# switches.net
KiCad netlist of a schematic drawn in Altium Designer
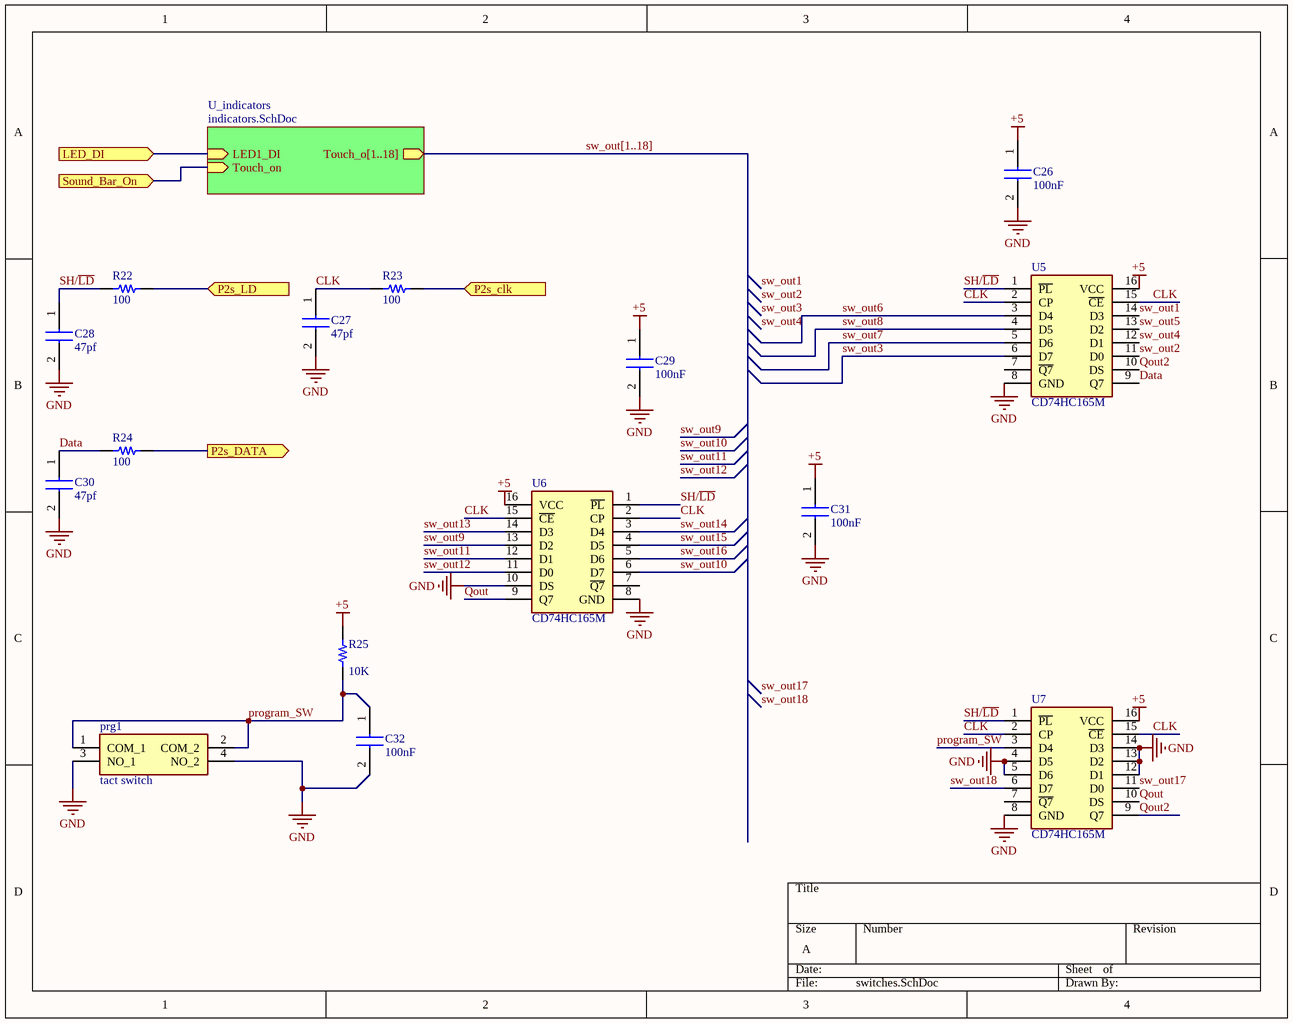
[diagram p0: switches.SchDoc]

(export (version "E")
  (design (tool "Eeschema 10.0.6"))
  (components
    (comp (ref "C26")
      (value "100nF")
      (footprint "0603C")
      (description "100 nF Ceramic capacitor")
      (fields
        (field (name "MANUFACTURER_PART_NUMBER") "C1206C104Z5UACTU")
        (field (name "MOUSER PART NUMBER") "80-C1206C104Z5U")
      )
      (libsource (lib "*") (part "C1206C104Z5UACTU"))
    )
    (comp (ref "C27")
      (value "47pf")
      (footprint "0603C")
      (description "100 nF Ceramic capacitor")
      (fields
        (field (name "MANUFACTURER_PART_NUMBER") "C1206C104Z5UACTU")
        (field (name "MOUSER PART NUMBER") "80-C1206C104Z5U")
      )
      (libsource (lib "*") (part "C1206C104Z5UACTU"))
    )
    (comp (ref "C28")
      (value "47pf")
      (footprint "0603C")
      (description "100 nF Ceramic capacitor")
      (fields
        (field (name "MANUFACTURER_PART_NUMBER") "C1206C104Z5UACTU")
        (field (name "MOUSER PART NUMBER") "80-C1206C104Z5U")
      )
      (libsource (lib "*") (part "C1206C104Z5UACTU"))
    )
    (comp (ref "C29")
      (value "100nF")
      (footprint "0603C")
      (description "100 nF Ceramic capacitor")
      (fields
        (field (name "MANUFACTURER_PART_NUMBER") "C1206C104Z5UACTU")
        (field (name "MOUSER PART NUMBER") "80-C1206C104Z5U")
      )
      (libsource (lib "*") (part "C1206C104Z5UACTU"))
    )
    (comp (ref "C30")
      (value "47pf")
      (footprint "0603C")
      (description "100 nF Ceramic capacitor")
      (fields
        (field (name "MANUFACTURER_PART_NUMBER") "C1206C104Z5UACTU")
        (field (name "MOUSER PART NUMBER") "80-C1206C104Z5U")
      )
      (libsource (lib "*") (part "C1206C104Z5UACTU"))
    )
    (comp (ref "C31")
      (value "100nF")
      (footprint "0603C")
      (description "100 nF Ceramic capacitor")
      (fields
        (field (name "MANUFACTURER_PART_NUMBER") "C1206C104Z5UACTU")
        (field (name "MOUSER PART NUMBER") "80-C1206C104Z5U")
      )
      (libsource (lib "*") (part "C1206C104Z5UACTU"))
    )
    (comp (ref "C32")
      (value "100nF")
      (footprint "0603C")
      (description "100 nF Ceramic capacitor")
      (fields
        (field (name "MANUFACTURER_PART_NUMBER") "C1206C104Z5UACTU")
        (field (name "MOUSER PART NUMBER") "80-C1206C104Z5U")
      )
      (libsource (lib "*") (part "C1206C104Z5UACTU"))
    )
    (comp (ref "prg1")
      (value "tact switch")
      (footprint "DTSM63NVB")
      (description "Push Button SMD - 4PIN")
      (fields
        (field (name "MANUFACTURER_PART_NUMBER") "DTSM-66R-V-T/R")
        (field (name "MOUSER PART NUMBER") "113-DTSM66RVTR")
      )
      (libsource (lib "*") (part "DTSM-66R-V-T_R"))
    )
    (comp (ref "R22")
      (value "100")
      (footprint "0603R")
      (description "RES SMD 10K OHM 5% 1/8W 0805")
      (fields (field (name "PART NUMBER") "CRCW080510K0JNEAIF") (field (name "MANUFACTURER") "Vishay Dale"))
      (libsource (lib "Celestial Altium Library - altium_library") (part "Resistor"))
    )
    (comp (ref "R23")
      (value "100")
      (footprint "0603R")
      (description "RES SMD 10K OHM 5% 1/8W 0805")
      (fields (field (name "PART NUMBER") "CRCW080510K0JNEAIF") (field (name "MANUFACTURER") "Vishay Dale"))
      (libsource (lib "Celestial Altium Library - altium_library") (part "Resistor"))
    )
    (comp (ref "R24")
      (value "100")
      (footprint "RES1206 _(3216X08L)")
      (description "RES SMD 10K OHM 5% 1/8W 0805")
      (fields (field (name "PART NUMBER") "CRCW080510K0JNEAIF") (field (name "MANUFACTURER") "Vishay Dale"))
      (libsource (lib "Celestial Altium Library - altium_library") (part "Resistor"))
    )
    (comp (ref "R25")
      (value "10K")
      (footprint "0603R")
      (description "RES SMD 0603")
      (fields (field (name "PART NUMBER") "RCS0805100KFKEA"))
      (libsource (lib "lamp control-ver2") (part "Resistor"))
    )
    (comp (ref "U5")
      (value "CD74HC165M")
      (footprint "SOIC127P600X175-16N")
      (description "Integrated Circuit")
      (fields (field (name "MOUSER PART NUMBER") "595-CD74HC165M"))
      (libsource (lib "SamacSys") (part "CD74HC165M"))
    )
    (comp (ref "U6")
      (value "CD74HC165M")
      (footprint "SOIC127P600X175-16N")
      (description "Integrated Circuit")
      (fields (field (name "MOUSER PART NUMBER") "595-CD74HC165M"))
      (libsource (lib "") (part "CD74HC165M_1"))
    )
    (comp (ref "U7")
      (value "CD74HC165M")
      (footprint "SOIC127P600X175-16N")
      (description "Integrated Circuit")
      (fields (field (name "MOUSER PART NUMBER") "595-CD74HC165M"))
      (libsource (lib "SamacSys") (part "CD74HC165M"))
    )
  )
  (nets
    (net (code "1") (name "+5") (class "Default")
      (node (ref "C26") (pin "1") (pinfunction "1_1") (pintype "passive"))
      (node (ref "C29") (pin "1") (pinfunction "1_1") (pintype "passive"))
      (node (ref "C31") (pin "1") (pinfunction "1_1") (pintype "passive"))
      (node (ref "R25") (pin "2") (pinfunction "2_2") (pintype "passive"))
      (node (ref "U5") (pin "16") (pinfunction "VCC_16") (pintype "passive"))
      (node (ref "U6") (pin "16") (pinfunction "VCC_16") (pintype "passive"))
      (node (ref "U7") (pin "16") (pinfunction "VCC_16") (pintype "passive"))
    )
    (net (code "2") (name "/CLK") (class "Default")
      (node (ref "C27") (pin "1") (pinfunction "1_1") (pintype "passive"))
      (node (ref "R23") (pin "2") (pinfunction "2_2") (pintype "passive"))
      (node (ref "U5") (pin "15") (pinfunction "~{CE}_15") (pintype "passive"))
      (node (ref "U5") (pin "2") (pinfunction "CP_2") (pintype "passive"))
      (node (ref "U6") (pin "15") (pinfunction "~{CE}_15") (pintype "passive"))
      (node (ref "U6") (pin "2") (pinfunction "CP_2") (pintype "passive"))
      (node (ref "U7") (pin "15") (pinfunction "~{CE}_15") (pintype "passive"))
      (node (ref "U7") (pin "2") (pinfunction "CP_2") (pintype "passive"))
    )
    (net (code "3") (name "/Data") (class "Default")
      (node (ref "C30") (pin "1") (pinfunction "1_1") (pintype "passive"))
      (node (ref "R24") (pin "2") (pinfunction "2_2") (pintype "passive"))
      (node (ref "U5") (pin "9") (pinfunction "Q7_9") (pintype "passive"))
    )
    (net (code "5") (name "/P2s_DATA") (class "Default")
      (node (ref "R24") (pin "1") (pinfunction "1_1") (pintype "passive"))
    )
    (net (code "6") (name "/P2s_LD") (class "Default")
      (node (ref "R22") (pin "1") (pinfunction "1_1") (pintype "passive"))
    )
    (net (code "7") (name "/P2s_clk") (class "Default")
      (node (ref "R23") (pin "1") (pinfunction "1_1") (pintype "passive"))
    )
    (net (code "8") (name "/Qout") (class "Default")
      (node (ref "U6") (pin "9") (pinfunction "Q7_9") (pintype "passive"))
      (node (ref "U7") (pin "10") (pinfunction "DS_10") (pintype "passive"))
    )
    (net (code "9") (name "/Qout2") (class "Default")
      (node (ref "U5") (pin "10") (pinfunction "DS_10") (pintype "passive"))
      (node (ref "U7") (pin "9") (pinfunction "Q7_9") (pintype "passive"))
    )
    (net (code "10") (name "/SH{slash}~{LD}") (class "Default")
      (node (ref "C28") (pin "1") (pinfunction "1_1") (pintype "passive"))
      (node (ref "R22") (pin "2") (pinfunction "2_2") (pintype "passive"))
      (node (ref "U5") (pin "1") (pinfunction "~{PL}_1") (pintype "passive"))
      (node (ref "U6") (pin "1") (pinfunction "~{PL}_1") (pintype "passive"))
      (node (ref "U7") (pin "1") (pinfunction "~{PL}_1") (pintype "passive"))
    )
    (net (code "12") (name "/program_SW") (class "Default")
      (node (ref "C32") (pin "1") (pinfunction "1_1") (pintype "passive"))
      (node (ref "R25") (pin "1") (pinfunction "1_1") (pintype "passive"))
      (node (ref "U7") (pin "3") (pinfunction "D4_3") (pintype "passive"))
      (node (ref "prg1") (pin "1") (pinfunction "COM_1_1") (pintype "passive"))
      (node (ref "prg1") (pin "2") (pinfunction "COM_2_2") (pintype "passive"))
    )
    (net (code "13") (name "/sw_out1") (class "Default")
      (node (ref "U5") (pin "14") (pinfunction "D3_14") (pintype "passive"))
    )
    (net (code "14") (name "/sw_out2") (class "Default")
      (node (ref "U5") (pin "11") (pinfunction "D0_11") (pintype "passive"))
    )
    (net (code "15") (name "/sw_out3") (class "Default")
      (node (ref "U5") (pin "6") (pinfunction "D7_6") (pintype "passive"))
    )
    (net (code "16") (name "/sw_out4") (class "Default")
      (node (ref "U5") (pin "12") (pinfunction "D1_12") (pintype "passive"))
    )
    (net (code "17") (name "/sw_out5") (class "Default")
      (node (ref "U5") (pin "13") (pinfunction "D2_13") (pintype "passive"))
    )
    (net (code "18") (name "/sw_out6") (class "Default")
      (node (ref "U5") (pin "3") (pinfunction "D4_3") (pintype "passive"))
    )
    (net (code "19") (name "/sw_out7") (class "Default")
      (node (ref "U5") (pin "5") (pinfunction "D6_5") (pintype "passive"))
    )
    (net (code "20") (name "/sw_out8") (class "Default")
      (node (ref "U5") (pin "4") (pinfunction "D5_4") (pintype "passive"))
    )
    (net (code "21") (name "/sw_out9") (class "Default")
      (node (ref "U6") (pin "13") (pinfunction "D2_13") (pintype "passive"))
    )
    (net (code "22") (name "/sw_out10") (class "Default")
      (node (ref "U6") (pin "6") (pinfunction "D7_6") (pintype "passive"))
    )
    (net (code "23") (name "/sw_out11") (class "Default")
      (node (ref "U6") (pin "12") (pinfunction "D1_12") (pintype "passive"))
    )
    (net (code "24") (name "/sw_out12") (class "Default")
      (node (ref "U6") (pin "11") (pinfunction "D0_11") (pintype "passive"))
    )
    (net (code "25") (name "/sw_out13") (class "Default")
      (node (ref "U6") (pin "14") (pinfunction "D3_14") (pintype "passive"))
    )
    (net (code "26") (name "/sw_out14") (class "Default")
      (node (ref "U6") (pin "3") (pinfunction "D4_3") (pintype "passive"))
    )
    (net (code "27") (name "/sw_out15") (class "Default")
      (node (ref "U6") (pin "4") (pinfunction "D5_4") (pintype "passive"))
    )
    (net (code "28") (name "/sw_out16") (class "Default")
      (node (ref "U6") (pin "5") (pinfunction "D6_5") (pintype "passive"))
    )
    (net (code "29") (name "/sw_out17") (class "Default")
      (node (ref "U7") (pin "11") (pinfunction "D0_11") (pintype "passive"))
    )
    (net (code "30") (name "/sw_out18") (class "Default")
      (node (ref "U7") (pin "6") (pinfunction "D7_6") (pintype "passive"))
    )
    (net (code "32") (name "GND") (class "Default")
      (node (ref "C26") (pin "2") (pinfunction "2_2") (pintype "passive"))
      (node (ref "C27") (pin "2") (pinfunction "2_2") (pintype "passive"))
      (node (ref "C28") (pin "2") (pinfunction "2_2") (pintype "passive"))
      (node (ref "C29") (pin "2") (pinfunction "2_2") (pintype "passive"))
      (node (ref "C30") (pin "2") (pinfunction "2_2") (pintype "passive"))
      (node (ref "C31") (pin "2") (pinfunction "2_2") (pintype "passive"))
      (node (ref "C32") (pin "2") (pinfunction "2_2") (pintype "passive"))
      (node (ref "U5") (pin "8") (pinfunction "GND_8") (pintype "passive"))
      (node (ref "U6") (pin "10") (pinfunction "DS_10") (pintype "passive"))
      (node (ref "U6") (pin "8") (pinfunction "GND_8") (pintype "passive"))
      (node (ref "U7") (pin "12") (pinfunction "D1_12") (pintype "passive"))
      (node (ref "U7") (pin "13") (pinfunction "D2_13") (pintype "passive"))
      (node (ref "U7") (pin "14") (pinfunction "D3_14") (pintype "passive"))
      (node (ref "U7") (pin "4") (pinfunction "D5_4") (pintype "passive"))
      (node (ref "U7") (pin "5") (pinfunction "D6_5") (pintype "passive"))
      (node (ref "U7") (pin "8") (pinfunction "GND_8") (pintype "passive"))
      (node (ref "prg1") (pin "3") (pinfunction "NO_1_3") (pintype "passive"))
      (node (ref "prg1") (pin "4") (pinfunction "NO_2_4") (pintype "passive"))
    )
    (net (code "33") (name "unconnected-(U5-~{Q7}-Pad7)") (class "Default")
      (node (ref "U5") (pin "7") (pinfunction "~{Q7}_7") (pintype "passive"))
    )
    (net (code "34") (name "unconnected-(U6-~{Q7}-Pad7)") (class "Default")
      (node (ref "U6") (pin "7") (pinfunction "~{Q7}_7") (pintype "passive"))
    )
    (net (code "35") (name "unconnected-(U7-~{Q7}-Pad7)") (class "Default")
      (node (ref "U7") (pin "7") (pinfunction "~{Q7}_7") (pintype "passive"))
    )
  )
)
